# i2clight_manual_route.net
KiCad netlist of a schematic drawn in EAGLE
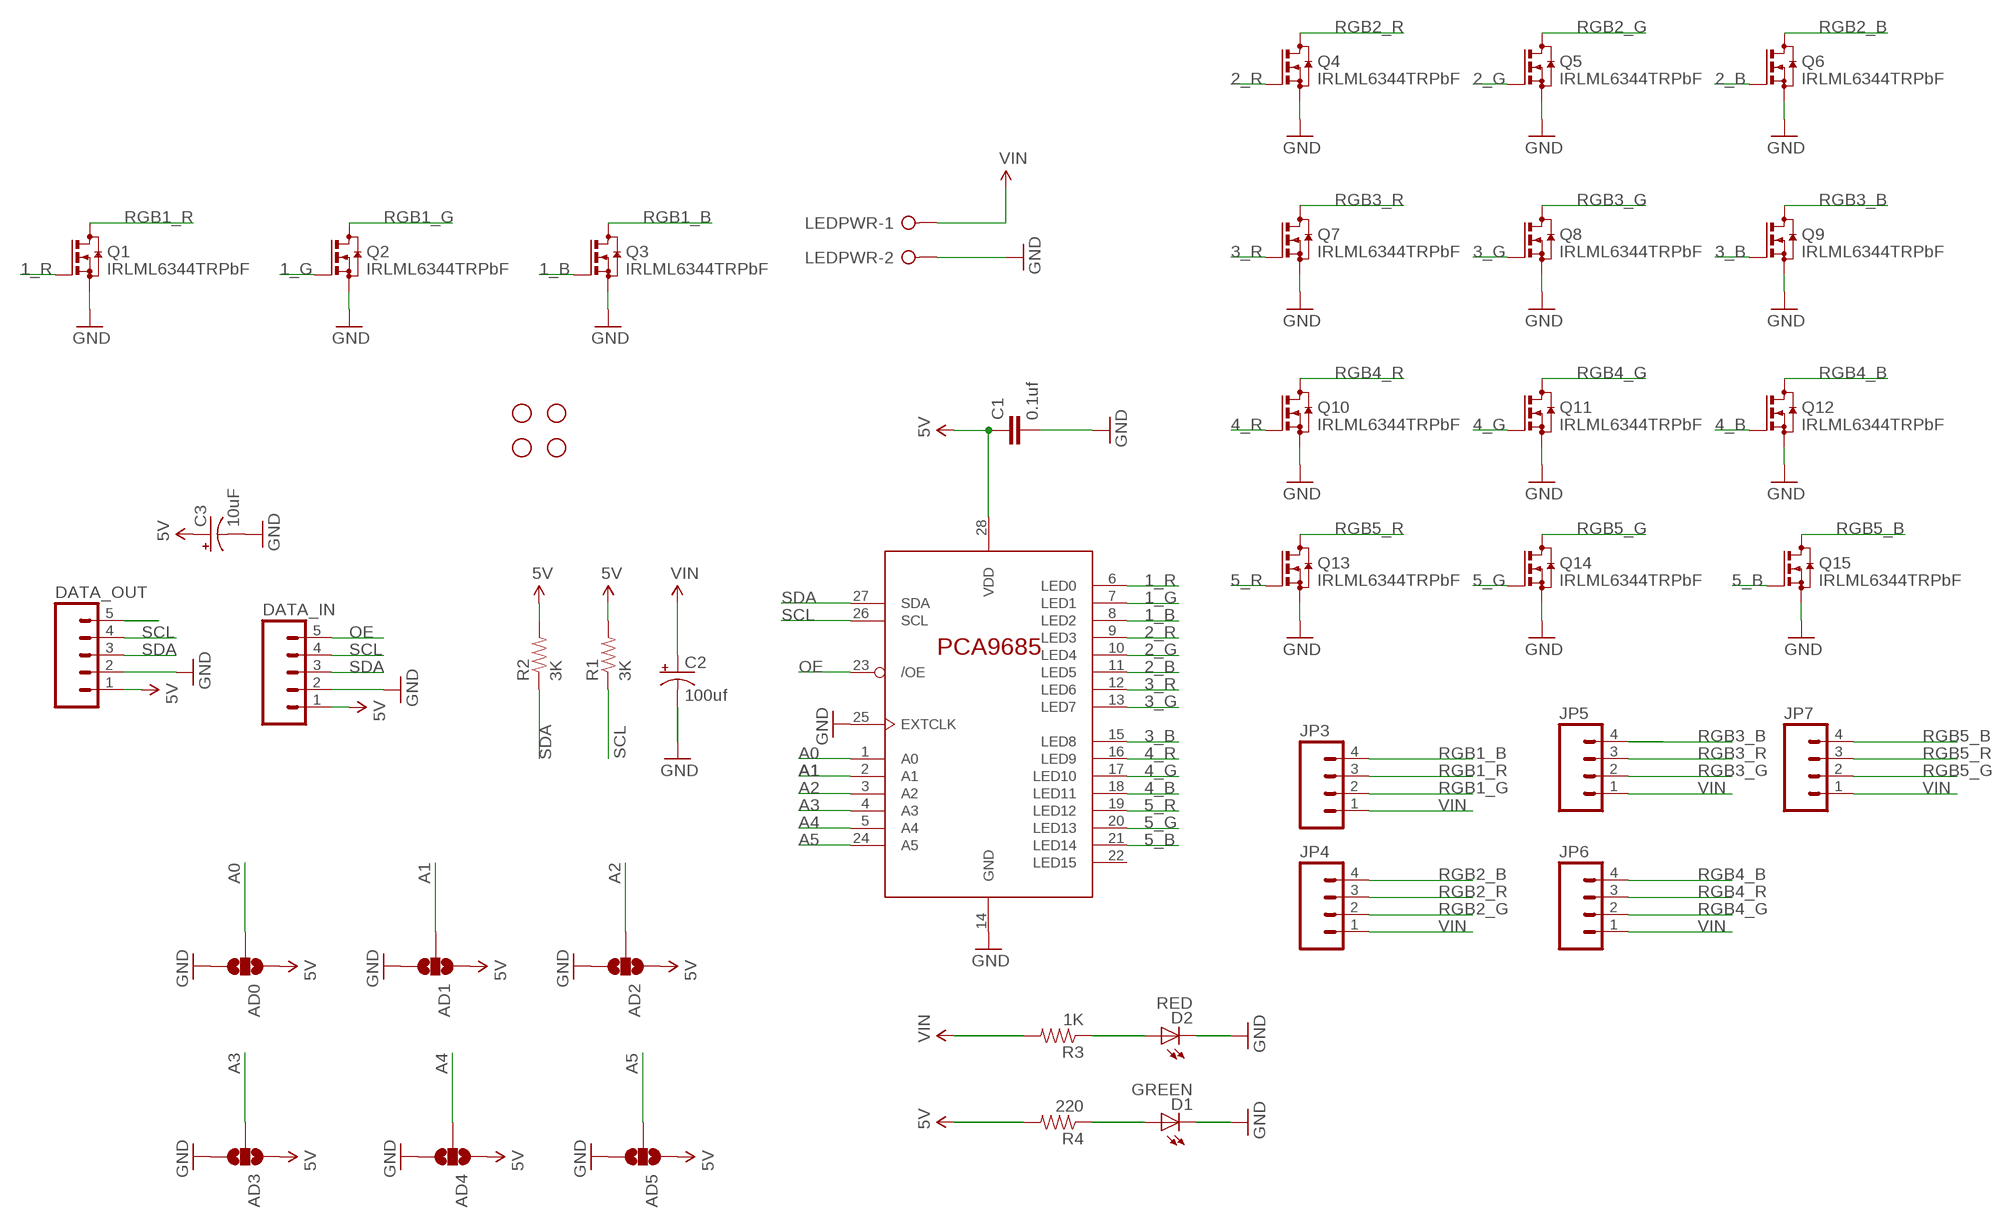
[diagram p0: schematic, sheet 1]

(export (version "E")
  (design (tool "Eeschema 10.0.6"))
  (components
    (comp (ref "AD0")
      (value "SOLDERJUMPER_2WAYT")
      (footprint "eagle-import:SJ_2")
      (libsource (lib "eagle-import") (part "SOLDERJUMPER_2WAYT"))
    )
    (comp (ref "AD1")
      (value "SOLDERJUMPER_2WAYT")
      (footprint "eagle-import:SJ_2")
      (libsource (lib "eagle-import") (part "SOLDERJUMPER_2WAYT"))
    )
    (comp (ref "AD2")
      (value "SOLDERJUMPER_2WAYT")
      (footprint "eagle-import:SJ_2")
      (libsource (lib "eagle-import") (part "SOLDERJUMPER_2WAYT"))
    )
    (comp (ref "AD3")
      (value "SOLDERJUMPER_2WAYT")
      (footprint "eagle-import:SJ_2")
      (libsource (lib "eagle-import") (part "SOLDERJUMPER_2WAYT"))
    )
    (comp (ref "AD4")
      (value "SOLDERJUMPER_2WAYT")
      (footprint "eagle-import:SJ_2")
      (libsource (lib "eagle-import") (part "SOLDERJUMPER_2WAYT"))
    )
    (comp (ref "AD5")
      (value "SOLDERJUMPER_2WAYT")
      (footprint "eagle-import:SJ_2")
      (libsource (lib "eagle-import") (part "SOLDERJUMPER_2WAYT"))
    )
    (comp (ref "C1")
      (value "0.1uf")
      (footprint "eagle-import:0805")
      (libsource (lib "eagle-import") (part "CAP0805"))
    )
    (comp (ref "C2")
      (value "100uf")
      (footprint "eagle-import:CPOL-RADIAL-100UF-25V")
      (libsource (lib "eagle-import") (part "CAP_POLPTH1"))
    )
    (comp (ref "C3")
      (value "10uF")
      (footprint "eagle-import:CPOL-RADIAL-10UF-25V")
      (libsource (lib "eagle-import") (part "CAP_POLPTH2"))
    )
    (comp (ref "D1")
      (value "GREEN")
      (footprint "eagle-import:LED-1206")
      (libsource (lib "eagle-import") (part "LED-GREENLARGE"))
    )
    (comp (ref "D2")
      (value "RED")
      (footprint "eagle-import:LED-1206")
      (libsource (lib "eagle-import") (part "LED-RED1206"))
    )
    (comp (ref "DATA_IN")
      (value "M05PTH_LONGPADS")
      (footprint "eagle-import:1X05_LONGPADS")
      (libsource (lib "eagle-import") (part "M05PTH_LONGPADS"))
    )
    (comp (ref "DATA_OUT")
      (value "M05PTH_LONGPADS")
      (footprint "eagle-import:1X05_LONGPADS")
      (libsource (lib "eagle-import") (part "M05PTH_LONGPADS"))
    )
    (comp (ref "JP3")
      (value "M04POLAR")
      (footprint "eagle-import:MOLEX-1X4")
      (libsource (lib "eagle-import") (part "M04POLAR"))
    )
    (comp (ref "JP4")
      (value "M04POLAR")
      (footprint "eagle-import:MOLEX-1X4")
      (libsource (lib "eagle-import") (part "M04POLAR"))
    )
    (comp (ref "JP5")
      (value "M04POLAR")
      (footprint "eagle-import:MOLEX-1X4")
      (libsource (lib "eagle-import") (part "M04POLAR"))
    )
    (comp (ref "JP6")
      (value "M04POLAR")
      (footprint "eagle-import:MOLEX-1X4")
      (libsource (lib "eagle-import") (part "M04POLAR"))
    )
    (comp (ref "JP7")
      (value "M04POLAR")
      (footprint "eagle-import:MOLEX-1X4")
      (libsource (lib "eagle-import") (part "M04POLAR"))
    )
    (comp (ref "LEDPWR")
      (value "W237-02P")
      (footprint "eagle-import:W237-132")
      (libsource (lib "eagle-import") (part "W237-02P"))
    )
    (comp (ref "PCA9685PW")
      (value "PCA9685PW")
      (footprint "eagle-import:TSSOP28")
      (libsource (lib "eagle-import") (part "PCA9685PW"))
    )
    (comp (ref "Q1")
      (value "IRLML6344TRPbF")
      (footprint "eagle-import:SOT23")
      (libsource (lib "eagle-import") (part "BSS123"))
    )
    (comp (ref "Q2")
      (value "IRLML6344TRPbF")
      (footprint "eagle-import:SOT23")
      (libsource (lib "eagle-import") (part "BSS123"))
    )
    (comp (ref "Q3")
      (value "IRLML6344TRPbF")
      (footprint "eagle-import:SOT23")
      (libsource (lib "eagle-import") (part "BSS123"))
    )
    (comp (ref "Q4")
      (value "IRLML6344TRPbF")
      (footprint "eagle-import:SOT23")
      (libsource (lib "eagle-import") (part "BSS123"))
    )
    (comp (ref "Q5")
      (value "IRLML6344TRPbF")
      (footprint "eagle-import:SOT23")
      (libsource (lib "eagle-import") (part "BSS123"))
    )
    (comp (ref "Q6")
      (value "IRLML6344TRPbF")
      (footprint "eagle-import:SOT23")
      (libsource (lib "eagle-import") (part "BSS123"))
    )
    (comp (ref "Q7")
      (value "IRLML6344TRPbF")
      (footprint "eagle-import:SOT23")
      (libsource (lib "eagle-import") (part "BSS123"))
    )
    (comp (ref "Q8")
      (value "IRLML6344TRPbF")
      (footprint "eagle-import:SOT23")
      (libsource (lib "eagle-import") (part "BSS123"))
    )
    (comp (ref "Q9")
      (value "IRLML6344TRPbF")
      (footprint "eagle-import:SOT23")
      (libsource (lib "eagle-import") (part "BSS123"))
    )
    (comp (ref "Q10")
      (value "IRLML6344TRPbF")
      (footprint "eagle-import:SOT23")
      (libsource (lib "eagle-import") (part "BSS123"))
    )
    (comp (ref "Q11")
      (value "IRLML6344TRPbF")
      (footprint "eagle-import:SOT23")
      (libsource (lib "eagle-import") (part "BSS123"))
    )
    (comp (ref "Q12")
      (value "IRLML6344TRPbF")
      (footprint "eagle-import:SOT23")
      (libsource (lib "eagle-import") (part "BSS123"))
    )
    (comp (ref "Q13")
      (value "IRLML6344TRPbF")
      (footprint "eagle-import:SOT23")
      (libsource (lib "eagle-import") (part "BSS123"))
    )
    (comp (ref "Q14")
      (value "IRLML6344TRPbF")
      (footprint "eagle-import:SOT23")
      (libsource (lib "eagle-import") (part "BSS123"))
    )
    (comp (ref "Q15")
      (value "IRLML6344TRPbF")
      (footprint "eagle-import:SOT23")
      (libsource (lib "eagle-import") (part "BSS123"))
    )
    (comp (ref "R1")
      (value "3K")
      (footprint "eagle-import:0805")
      (libsource (lib "eagle-import") (part "RESISTOR0805-RES"))
    )
    (comp (ref "R2")
      (value "3K")
      (footprint "eagle-import:0805")
      (libsource (lib "eagle-import") (part "RESISTOR0805-RES"))
    )
    (comp (ref "R3")
      (value "1K")
      (footprint "eagle-import:0805")
      (libsource (lib "eagle-import") (part "RESISTOR0805-RES"))
    )
    (comp (ref "R4")
      (value "220")
      (footprint "eagle-import:0805")
      (libsource (lib "eagle-import") (part "RESISTOR0805-RES"))
    )
    (comp (ref "STANDOFF1")
      (value "STAND-OFF")
      (footprint "eagle-import:STAND-OFF")
      (libsource (lib "eagle-import") (part "STAND-OFF"))
    )
    (comp (ref "STANDOFF2")
      (value "STAND-OFF")
      (footprint "eagle-import:STAND-OFF")
      (libsource (lib "eagle-import") (part "STAND-OFF"))
    )
    (comp (ref "STANDOFF3")
      (value "STAND-OFF")
      (footprint "eagle-import:STAND-OFF")
      (libsource (lib "eagle-import") (part "STAND-OFF"))
    )
    (comp (ref "STANDOFF4")
      (value "STAND-OFF")
      (footprint "eagle-import:STAND-OFF")
      (libsource (lib "eagle-import") (part "STAND-OFF"))
    )
  )
  (nets
    (net (code "1") (name "/1_B") (class "Default")
      (node (ref "PCA9685PW") (pin "8") (pinfunction "LED2_8") (pintype "bidirectional"))
      (node (ref "Q3") (pin "1") (pinfunction "G_1") (pintype "passive"))
    )
    (net (code "2") (name "/1_G") (class "Default")
      (node (ref "PCA9685PW") (pin "7") (pinfunction "LED1_7") (pintype "bidirectional"))
      (node (ref "Q2") (pin "1") (pinfunction "G_1") (pintype "passive"))
    )
    (net (code "3") (name "/1_R") (class "Default")
      (node (ref "PCA9685PW") (pin "6") (pinfunction "LED0_6") (pintype "bidirectional"))
      (node (ref "Q1") (pin "1") (pinfunction "G_1") (pintype "passive"))
    )
    (net (code "4") (name "/2_B") (class "Default")
      (node (ref "PCA9685PW") (pin "11") (pinfunction "LED5_11") (pintype "bidirectional"))
      (node (ref "Q6") (pin "1") (pinfunction "G_1") (pintype "passive"))
    )
    (net (code "5") (name "/2_G") (class "Default")
      (node (ref "PCA9685PW") (pin "10") (pinfunction "LED4_10") (pintype "bidirectional"))
      (node (ref "Q5") (pin "1") (pinfunction "G_1") (pintype "passive"))
    )
    (net (code "6") (name "/2_R") (class "Default")
      (node (ref "PCA9685PW") (pin "9") (pinfunction "LED3_9") (pintype "bidirectional"))
      (node (ref "Q4") (pin "1") (pinfunction "G_1") (pintype "passive"))
    )
    (net (code "7") (name "/3_B") (class "Default")
      (node (ref "PCA9685PW") (pin "15") (pinfunction "LED8_15") (pintype "bidirectional"))
      (node (ref "Q9") (pin "1") (pinfunction "G_1") (pintype "passive"))
    )
    (net (code "8") (name "/3_G") (class "Default")
      (node (ref "PCA9685PW") (pin "13") (pinfunction "LED7_13") (pintype "bidirectional"))
      (node (ref "Q8") (pin "1") (pinfunction "G_1") (pintype "passive"))
    )
    (net (code "9") (name "/3_R") (class "Default")
      (node (ref "PCA9685PW") (pin "12") (pinfunction "LED6_12") (pintype "bidirectional"))
      (node (ref "Q7") (pin "1") (pinfunction "G_1") (pintype "passive"))
    )
    (net (code "10") (name "/4_B") (class "Default")
      (node (ref "PCA9685PW") (pin "18") (pinfunction "LED11_18") (pintype "bidirectional"))
      (node (ref "Q12") (pin "1") (pinfunction "G_1") (pintype "passive"))
    )
    (net (code "11") (name "/4_G") (class "Default")
      (node (ref "PCA9685PW") (pin "17") (pinfunction "LED10_17") (pintype "bidirectional"))
      (node (ref "Q11") (pin "1") (pinfunction "G_1") (pintype "passive"))
    )
    (net (code "12") (name "/4_R") (class "Default")
      (node (ref "PCA9685PW") (pin "16") (pinfunction "LED9_16") (pintype "bidirectional"))
      (node (ref "Q10") (pin "1") (pinfunction "G_1") (pintype "passive"))
    )
    (net (code "13") (name "/5_B") (class "Default")
      (node (ref "PCA9685PW") (pin "21") (pinfunction "LED14_21") (pintype "bidirectional"))
      (node (ref "Q15") (pin "1") (pinfunction "G_1") (pintype "passive"))
    )
    (net (code "14") (name "/5_G") (class "Default")
      (node (ref "PCA9685PW") (pin "20") (pinfunction "LED13_20") (pintype "bidirectional"))
      (node (ref "Q14") (pin "1") (pinfunction "G_1") (pintype "passive"))
    )
    (net (code "15") (name "/5_R") (class "Default")
      (node (ref "PCA9685PW") (pin "19") (pinfunction "LED12_19") (pintype "bidirectional"))
      (node (ref "Q13") (pin "1") (pinfunction "G_1") (pintype "passive"))
    )
    (net (code "16") (name "/A0") (class "Default")
      (node (ref "AD0") (pin "2") (pinfunction "2_2") (pintype "passive"))
      (node (ref "PCA9685PW") (pin "1") (pinfunction "A0_1") (pintype "bidirectional"))
    )
    (net (code "17") (name "/A1") (class "Default")
      (node (ref "AD1") (pin "2") (pinfunction "2_2") (pintype "passive"))
      (node (ref "PCA9685PW") (pin "2") (pinfunction "A1_2") (pintype "bidirectional"))
    )
    (net (code "18") (name "/A2") (class "Default")
      (node (ref "AD2") (pin "2") (pinfunction "2_2") (pintype "passive"))
      (node (ref "PCA9685PW") (pin "3") (pinfunction "A2_3") (pintype "bidirectional"))
    )
    (net (code "19") (name "/A3") (class "Default")
      (node (ref "AD3") (pin "2") (pinfunction "2_2") (pintype "passive"))
      (node (ref "PCA9685PW") (pin "4") (pinfunction "A3_4") (pintype "bidirectional"))
    )
    (net (code "20") (name "/A4") (class "Default")
      (node (ref "AD4") (pin "2") (pinfunction "2_2") (pintype "passive"))
      (node (ref "PCA9685PW") (pin "5") (pinfunction "A4_5") (pintype "bidirectional"))
    )
    (net (code "21") (name "/A5") (class "Default")
      (node (ref "AD5") (pin "2") (pinfunction "2_2") (pintype "passive"))
      (node (ref "PCA9685PW") (pin "24") (pinfunction "A5_24") (pintype "bidirectional"))
    )
    (net (code "22") (name "/OE") (class "Default")
      (node (ref "DATA_IN") (pin "5") (pinfunction "5_5") (pintype "passive"))
      (node (ref "DATA_OUT") (pin "5") (pinfunction "5_5") (pintype "passive"))
      (node (ref "PCA9685PW") (pin "23") (pinfunction "/OE_23") (pintype "bidirectional"))
    )
    (net (code "23") (name "/RGB1_B") (class "Default")
      (node (ref "JP3") (pin "4") (pinfunction "4_4") (pintype "passive"))
      (node (ref "Q3") (pin "3") (pinfunction "D_3") (pintype "passive"))
    )
    (net (code "24") (name "/RGB1_G") (class "Default")
      (node (ref "JP3") (pin "2") (pinfunction "2_2") (pintype "passive"))
      (node (ref "Q2") (pin "3") (pinfunction "D_3") (pintype "passive"))
    )
    (net (code "25") (name "/RGB1_R") (class "Default")
      (node (ref "JP3") (pin "3") (pinfunction "3_3") (pintype "passive"))
      (node (ref "Q1") (pin "3") (pinfunction "D_3") (pintype "passive"))
    )
    (net (code "26") (name "/RGB2_B") (class "Default")
      (node (ref "JP4") (pin "4") (pinfunction "4_4") (pintype "passive"))
      (node (ref "Q6") (pin "3") (pinfunction "D_3") (pintype "passive"))
    )
    (net (code "27") (name "/RGB2_G") (class "Default")
      (node (ref "JP4") (pin "2") (pinfunction "2_2") (pintype "passive"))
      (node (ref "Q5") (pin "3") (pinfunction "D_3") (pintype "passive"))
    )
    (net (code "28") (name "/RGB2_R") (class "Default")
      (node (ref "JP4") (pin "3") (pinfunction "3_3") (pintype "passive"))
      (node (ref "Q4") (pin "3") (pinfunction "D_3") (pintype "passive"))
    )
    (net (code "29") (name "/RGB3_B") (class "Default")
      (node (ref "JP5") (pin "4") (pinfunction "4_4") (pintype "passive"))
      (node (ref "Q9") (pin "3") (pinfunction "D_3") (pintype "passive"))
    )
    (net (code "30") (name "/RGB3_G") (class "Default")
      (node (ref "JP5") (pin "2") (pinfunction "2_2") (pintype "passive"))
      (node (ref "Q8") (pin "3") (pinfunction "D_3") (pintype "passive"))
    )
    (net (code "31") (name "/RGB3_R") (class "Default")
      (node (ref "JP5") (pin "3") (pinfunction "3_3") (pintype "passive"))
      (node (ref "Q7") (pin "3") (pinfunction "D_3") (pintype "passive"))
    )
    (net (code "32") (name "/RGB4_B") (class "Default")
      (node (ref "JP6") (pin "4") (pinfunction "4_4") (pintype "passive"))
      (node (ref "Q12") (pin "3") (pinfunction "D_3") (pintype "passive"))
    )
    (net (code "33") (name "/RGB4_G") (class "Default")
      (node (ref "JP6") (pin "2") (pinfunction "2_2") (pintype "passive"))
      (node (ref "Q11") (pin "3") (pinfunction "D_3") (pintype "passive"))
    )
    (net (code "34") (name "/RGB4_R") (class "Default")
      (node (ref "JP6") (pin "3") (pinfunction "3_3") (pintype "passive"))
      (node (ref "Q10") (pin "3") (pinfunction "D_3") (pintype "passive"))
    )
    (net (code "35") (name "/RGB5_B") (class "Default")
      (node (ref "JP7") (pin "4") (pinfunction "4_4") (pintype "passive"))
      (node (ref "Q15") (pin "3") (pinfunction "D_3") (pintype "passive"))
    )
    (net (code "36") (name "/RGB5_G") (class "Default")
      (node (ref "JP7") (pin "2") (pinfunction "2_2") (pintype "passive"))
      (node (ref "Q14") (pin "3") (pinfunction "D_3") (pintype "passive"))
    )
    (net (code "37") (name "/RGB5_R") (class "Default")
      (node (ref "JP7") (pin "3") (pinfunction "3_3") (pintype "passive"))
      (node (ref "Q13") (pin "3") (pinfunction "D_3") (pintype "passive"))
    )
    (net (code "38") (name "/SCL") (class "Default")
      (node (ref "DATA_IN") (pin "4") (pinfunction "4_4") (pintype "passive"))
      (node (ref "DATA_OUT") (pin "4") (pinfunction "4_4") (pintype "passive"))
      (node (ref "PCA9685PW") (pin "26") (pinfunction "SCL_26") (pintype "bidirectional"))
      (node (ref "R1") (pin "1") (pinfunction "1_1") (pintype "passive"))
    )
    (net (code "39") (name "/SDA") (class "Default")
      (node (ref "DATA_IN") (pin "3") (pinfunction "3_3") (pintype "passive"))
      (node (ref "DATA_OUT") (pin "3") (pinfunction "3_3") (pintype "passive"))
      (node (ref "PCA9685PW") (pin "27") (pinfunction "SDA_27") (pintype "bidirectional"))
      (node (ref "R2") (pin "1") (pinfunction "1_1") (pintype "passive"))
    )
    (net (code "40") (name "5V") (class "Default")
      (node (ref "AD0") (pin "1") (pinfunction "1_1") (pintype "passive"))
      (node (ref "AD1") (pin "1") (pinfunction "1_1") (pintype "passive"))
      (node (ref "AD2") (pin "1") (pinfunction "1_1") (pintype "passive"))
      (node (ref "AD3") (pin "1") (pinfunction "1_1") (pintype "passive"))
      (node (ref "AD4") (pin "1") (pinfunction "1_1") (pintype "passive"))
      (node (ref "AD5") (pin "1") (pinfunction "1_1") (pintype "passive"))
      (node (ref "C1") (pin "1") (pinfunction "1_1") (pintype "passive"))
      (node (ref "C3") (pin "1") (pinfunction "+_1") (pintype "passive"))
      (node (ref "DATA_IN") (pin "1") (pinfunction "1_1") (pintype "passive"))
      (node (ref "DATA_OUT") (pin "1") (pinfunction "1_1") (pintype "passive"))
      (node (ref "PCA9685PW") (pin "28") (pinfunction "VDD_28") (pintype "power_in"))
      (node (ref "R1") (pin "2") (pinfunction "2_2") (pintype "passive"))
      (node (ref "R2") (pin "2") (pinfunction "2_2") (pintype "passive"))
      (node (ref "R4") (pin "2") (pinfunction "2_2") (pintype "passive"))
    )
    (net (code "41") (name "GND") (class "Default")
      (node (ref "AD0") (pin "3") (pinfunction "3_3") (pintype "passive"))
      (node (ref "AD1") (pin "3") (pinfunction "3_3") (pintype "passive"))
      (node (ref "AD2") (pin "3") (pinfunction "3_3") (pintype "passive"))
      (node (ref "AD3") (pin "3") (pinfunction "3_3") (pintype "passive"))
      (node (ref "AD4") (pin "3") (pinfunction "3_3") (pintype "passive"))
      (node (ref "AD5") (pin "3") (pinfunction "3_3") (pintype "passive"))
      (node (ref "C1") (pin "2") (pinfunction "2_2") (pintype "passive"))
      (node (ref "C2") (pin "2") (pinfunction "-_2") (pintype "passive"))
      (node (ref "C3") (pin "2") (pinfunction "-_2") (pintype "passive"))
      (node (ref "D1") (pin "C") (pinfunction "C_C") (pintype "passive"))
      (node (ref "D2") (pin "C") (pinfunction "C_C") (pintype "passive"))
      (node (ref "DATA_IN") (pin "2") (pinfunction "2_2") (pintype "passive"))
      (node (ref "DATA_OUT") (pin "2") (pinfunction "2_2") (pintype "passive"))
      (node (ref "LEDPWR") (pin "2") (pinfunction "KL_2") (pintype "passive"))
      (node (ref "PCA9685PW") (pin "14") (pinfunction "GND_14") (pintype "power_in"))
      (node (ref "PCA9685PW") (pin "25") (pinfunction "EXTCLK_25") (pintype "input"))
      (node (ref "Q1") (pin "2") (pinfunction "S_2") (pintype "passive"))
      (node (ref "Q10") (pin "2") (pinfunction "S_2") (pintype "passive"))
      (node (ref "Q11") (pin "2") (pinfunction "S_2") (pintype "passive"))
      (node (ref "Q12") (pin "2") (pinfunction "S_2") (pintype "passive"))
      (node (ref "Q13") (pin "2") (pinfunction "S_2") (pintype "passive"))
      (node (ref "Q14") (pin "2") (pinfunction "S_2") (pintype "passive"))
      (node (ref "Q15") (pin "2") (pinfunction "S_2") (pintype "passive"))
      (node (ref "Q2") (pin "2") (pinfunction "S_2") (pintype "passive"))
      (node (ref "Q3") (pin "2") (pinfunction "S_2") (pintype "passive"))
      (node (ref "Q4") (pin "2") (pinfunction "S_2") (pintype "passive"))
      (node (ref "Q5") (pin "2") (pinfunction "S_2") (pintype "passive"))
      (node (ref "Q6") (pin "2") (pinfunction "S_2") (pintype "passive"))
      (node (ref "Q7") (pin "2") (pinfunction "S_2") (pintype "passive"))
      (node (ref "Q8") (pin "2") (pinfunction "S_2") (pintype "passive"))
      (node (ref "Q9") (pin "2") (pinfunction "S_2") (pintype "passive"))
    )
    (net (code "42") (name "Net-(D1-PadA)") (class "Default")
      (node (ref "D1") (pin "A") (pinfunction "A_A") (pintype "passive"))
      (node (ref "R4") (pin "1") (pinfunction "1_1") (pintype "passive"))
    )
    (net (code "43") (name "Net-(D2-PadA)") (class "Default")
      (node (ref "D2") (pin "A") (pinfunction "A_A") (pintype "passive"))
      (node (ref "R3") (pin "1") (pinfunction "1_1") (pintype "passive"))
    )
    (net (code "44") (name "VIN") (class "Default")
      (node (ref "C2") (pin "1") (pinfunction "+_1") (pintype "passive"))
      (node (ref "JP3") (pin "1") (pinfunction "1_1") (pintype "passive"))
      (node (ref "JP4") (pin "1") (pinfunction "1_1") (pintype "passive"))
      (node (ref "JP5") (pin "1") (pinfunction "1_1") (pintype "passive"))
      (node (ref "JP6") (pin "1") (pinfunction "1_1") (pintype "passive"))
      (node (ref "JP7") (pin "1") (pinfunction "1_1") (pintype "passive"))
      (node (ref "LEDPWR") (pin "1") (pinfunction "KL_1") (pintype "passive"))
      (node (ref "R3") (pin "2") (pinfunction "2_2") (pintype "passive"))
    )
    (net (code "45") (name "unconnected-(PCA9685PW-LED15-Pad22)") (class "Default")
      (node (ref "PCA9685PW") (pin "22") (pinfunction "LED15_22") (pintype "bidirectional"))
    )
  )
)
